# Mainboard_V1_0_Ethernet.net
KiCad netlist of a schematic drawn in Altium Designer
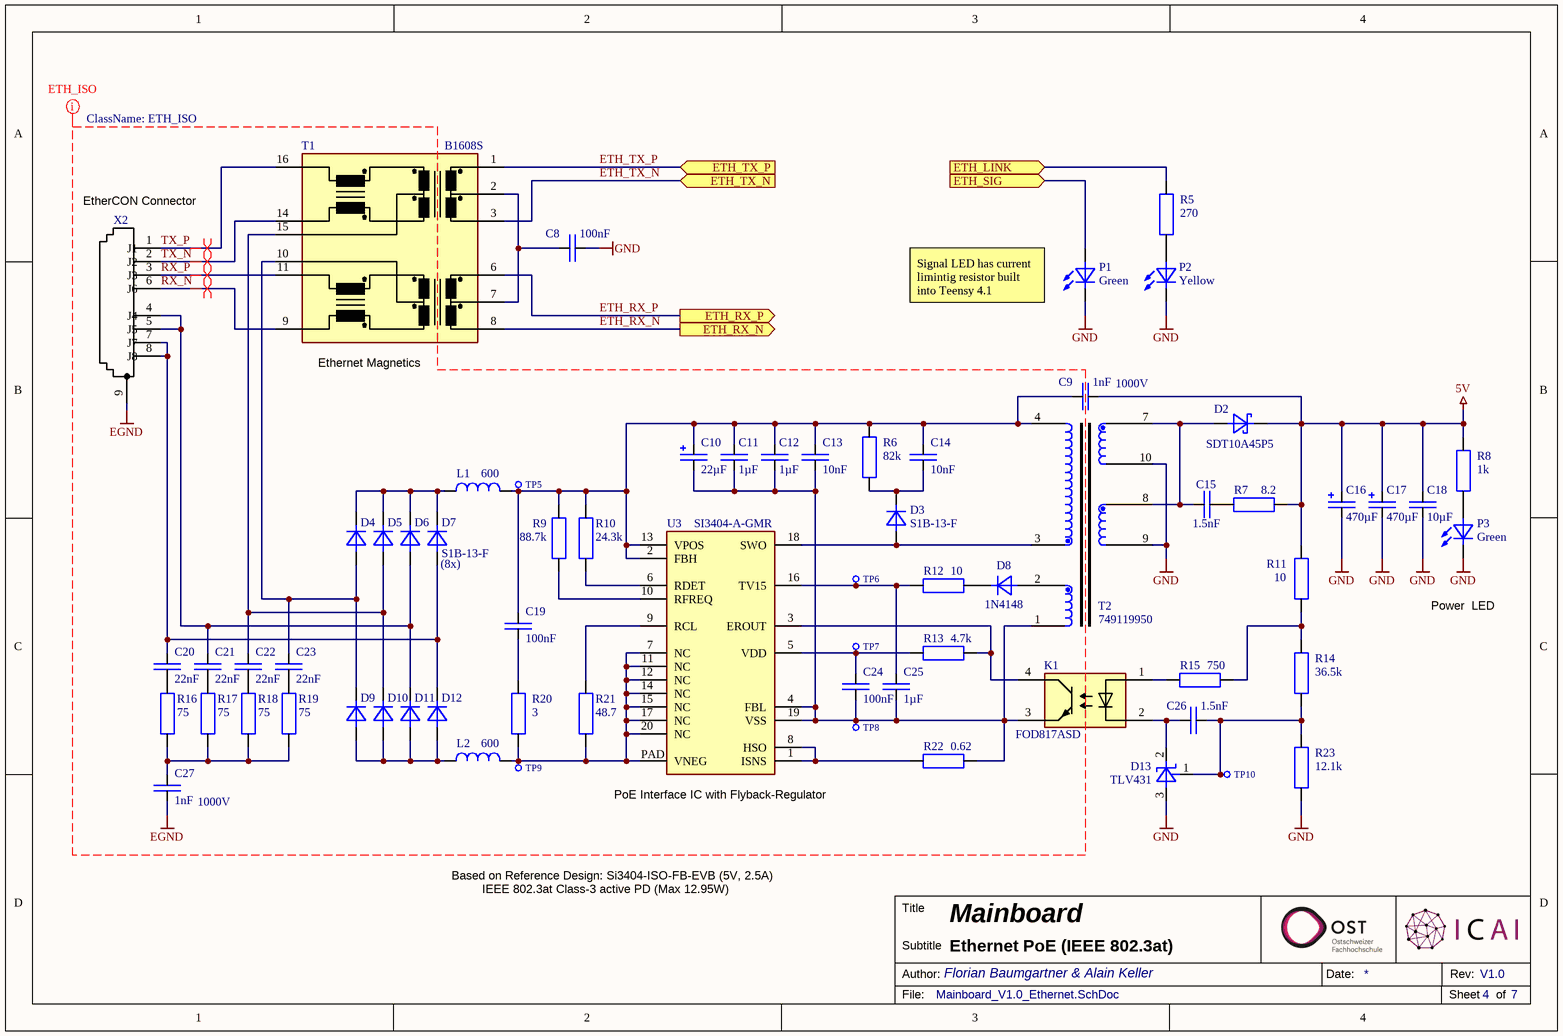
[diagram p0: Mainboard_V1.0_Ethernet.SchDoc]

(export (version "E")
  (design (tool "Eeschema 10.0.6"))
  (components
    (comp (ref "C8")
      (value "100nF")
      (footprint "SMD Keramikkondensator 0603")
      (description "SMD Ceramic Capacitor E6")
      (libsource (lib "Ceramic Capacitors-E6") (part "E6 - 100nF"))
    )
    (comp (ref "C9")
      (value "1nF")
      (footprint "SMD KERAMIKKONDENSATOR 1808")
      (description "SMD Ceramic Capacitor E6")
      (libsource (lib "Ceramic Capacitors-E6") (part "E6 - 1nF"))
    )
    (comp (ref "C10")
      (value "22µF")
      (footprint "SMD Elko 6.3x7.7")
      (description "CAP-Elko")
      (libsource (lib "TFS Integrated Library") (part "C-ELCAP"))
    )
    (comp (ref "C11")
      (value "1µF")
      (footprint "SMD Keramikkondensator 1206")
      (description "CAP-MK")
      (libsource (lib "AudioAmp") (part "C-CAPACITOR"))
    )
    (comp (ref "C12")
      (value "1µF")
      (footprint "SMD Keramikkondensator 1206")
      (description "CAP-MK")
      (libsource (lib "AudioAmp") (part "C-CAPACITOR"))
    )
    (comp (ref "C13")
      (value "10nF")
      (footprint "SMD Keramikkondensator 0603")
      (description "SMD Ceramic Capacitor E6")
      (libsource (lib "Ceramic Capacitors-E6") (part "E6 - 22nF"))
    )
    (comp (ref "C14")
      (value "10nF")
      (footprint "SMD Keramikkondensator 0603")
      (description "SMD Ceramic Capacitor E6")
      (libsource (lib "Ceramic Capacitors-E6") (part "E6 - 22nF"))
    )
    (comp (ref "C15")
      (value "1.5nF")
      (footprint "SMD Keramikkondensator 0603")
      (description "CAP-MK")
      (libsource (lib "AudioAmp") (part "C-CAPACITOR"))
    )
    (comp (ref "C16")
      (value "470µF")
      (footprint "SMD Elko 6.3x7.7")
      (description "CAP-Elko")
      (libsource (lib "TFS Integrated Library") (part "C-ELCAP"))
    )
    (comp (ref "C17")
      (value "470µF")
      (footprint "SMD Elko 6.3x7.7")
      (description "CAP-Elko")
      (libsource (lib "TFS Integrated Library") (part "C-ELCAP"))
    )
    (comp (ref "C18")
      (value "10µF")
      (footprint "SMD Keramikkondensator 1206")
      (description "SMD Ceramic Capacitor E6")
      (libsource (lib "Ceramic Capacitors-E6") (part "E6 - 10uF"))
    )
    (comp (ref "C19")
      (value "100nF")
      (footprint "SMD Keramikkondensator 0805")
      (description "SMD Ceramic Capacitor E6")
      (libsource (lib "Ceramic Capacitors-E6") (part "E6 - 22nF"))
    )
    (comp (ref "C20")
      (value "22nF")
      (footprint "SMD Keramikkondensator 0603")
      (description "SMD Ceramic Capacitor E6")
      (libsource (lib "Ceramic Capacitors-E6") (part "E6 - 22nF"))
    )
    (comp (ref "C21")
      (value "22nF")
      (footprint "SMD Keramikkondensator 0603")
      (description "SMD Ceramic Capacitor E6")
      (libsource (lib "Ceramic Capacitors-E6") (part "E6 - 22nF"))
    )
    (comp (ref "C22")
      (value "22nF")
      (footprint "SMD Keramikkondensator 0603")
      (description "SMD Ceramic Capacitor E6")
      (libsource (lib "Ceramic Capacitors-E6") (part "E6 - 22nF"))
    )
    (comp (ref "C23")
      (value "22nF")
      (footprint "SMD Keramikkondensator 0603")
      (description "SMD Ceramic Capacitor E6")
      (libsource (lib "Ceramic Capacitors-E6") (part "E6 - 22nF"))
    )
    (comp (ref "C24")
      (value "100nF")
      (footprint "SMD Keramikkondensator 0603")
      (description "SMD Ceramic Capacitor E6")
      (libsource (lib "Ceramic Capacitors-E6") (part "E6 - 100nF"))
    )
    (comp (ref "C25")
      (value "1µF")
      (footprint "SMD Keramikkondensator 0603")
      (description "CAP-MK")
      (libsource (lib "AudioAmp") (part "C-CAPACITOR"))
    )
    (comp (ref "C26")
      (value "1.5nF")
      (footprint "SMD Keramikkondensator 0603")
      (description "CAP-MK")
      (libsource (lib "AudioAmp") (part "C-CAPACITOR"))
    )
    (comp (ref "C27")
      (value "1nF")
      (footprint "SMD KERAMIKKONDENSATOR 1808")
      (description "SMD Ceramic Capacitor E6")
      (libsource (lib "Ceramic Capacitors-E6") (part "E6 - 1nF"))
    )
    (comp (ref "D2")
      (value "SDT10A45P5")
      (footprint "SMD Diode PowerDI-5")
      (description "Trench Schottky Barrier Rectifier")
      (libsource (lib "TFS Integrated Library") (part "R-DIODE{colon}SCHKY"))
    )
    (comp (ref "D3")
      (value "S1B-13-F")
      (footprint "SMD Diode DO-214-AC")
      (description "DIODE (alt V)")
      (libsource (lib "TFS Integrated Library") (part "R-DIODE"))
    )
    (comp (ref "D4")
      (value "S1B-13-F")
      (footprint "SMD Diode DO-214-AC")
      (description "DIODE (alt V)")
      (libsource (lib "TFS Integrated Library") (part "R-DIODE"))
    )
    (comp (ref "D5")
      (value "S1B-13-F")
      (footprint "SMD Diode DO-214-AC")
      (description "DIODE (alt V)")
      (libsource (lib "TFS Integrated Library") (part "R-DIODE"))
    )
    (comp (ref "D6")
      (value "S1B-13-F")
      (footprint "SMD Diode DO-214-AC")
      (description "DIODE (alt V)")
      (libsource (lib "TFS Integrated Library") (part "R-DIODE"))
    )
    (comp (ref "D7")
      (value "S1B-13-F")
      (footprint "SMD Diode DO-214-AC")
      (description "DIODE (alt V)")
      (libsource (lib "TFS Integrated Library") (part "R-DIODE"))
    )
    (comp (ref "D8")
      (value "1N4148")
      (footprint "SMD Diode SOD-123")
      (description "DIODE (alt V)")
      (libsource (lib "TFS Integrated Library") (part "R-DIODE"))
    )
    (comp (ref "D9")
      (value "S1B-13-F")
      (footprint "SMD Diode DO-214-AC")
      (description "DIODE (alt V)")
      (libsource (lib "TFS Integrated Library") (part "R-DIODE"))
    )
    (comp (ref "D10")
      (value "S1B-13-F")
      (footprint "SMD Diode DO-214-AC")
      (description "DIODE (alt V)")
      (libsource (lib "TFS Integrated Library") (part "R-DIODE"))
    )
    (comp (ref "D11")
      (value "S1B-13-F")
      (footprint "SMD Diode DO-214-AC")
      (description "DIODE (alt V)")
      (libsource (lib "TFS Integrated Library") (part "R-DIODE"))
    )
    (comp (ref "D12")
      (value "S1B-13-F")
      (footprint "SMD Diode DO-214-AC")
      (description "DIODE (alt V)")
      (libsource (lib "TFS Integrated Library") (part "R-DIODE"))
    )
    (comp (ref "D13")
      (value "TLV431")
      (footprint "SMD IC SOT-23-3")
      (description "Low-Voltage Adjustable Precision Shunt Regulator")
      (libsource (lib "Mainboard") (part "D-Voltage-Refference"))
    )
    (comp (ref "K1")
      (value "FOD817ASD")
      (footprint "SMD IC DIP-4")
      (description "Phototransistor Optocoupler")
      (libsource (lib "Mainboard") (part "K-FOD817ASD"))
    )
    (comp (ref "L1")
      (value "600")
      (footprint "SMD INDUCTOR/FERRITE 0805")
      (description "COIL (Spule alt L)")
      (libsource (lib "TFS Integrated Library") (part "R-COIL (HF)"))
    )
    (comp (ref "L2")
      (value "600")
      (footprint "SMD INDUCTOR/FERRITE 0805")
      (description "COIL (Spule alt L)")
      (libsource (lib "TFS Integrated Library") (part "R-COIL (HF)"))
    )
    (comp (ref "P1")
      (value "Green")
      (footprint "SMD LED 0603")
      (description "LED (als Lampe E / alt H)")
      (libsource (lib "TFS Integrated Library") (part "P-LED"))
    )
    (comp (ref "P2")
      (value "Yellow")
      (footprint "SMD LED 0603")
      (description "LED (als Lampe E / alt H)")
      (libsource (lib "TFS Integrated Library") (part "P-LED"))
    )
    (comp (ref "P3")
      (value "Green")
      (footprint "SMD LED 0603")
      (description "General Purpose LED")
      (libsource (lib "Fleet-Monitor") (part "LED Green 0603"))
    )
    (comp (ref "R5")
      (value "270")
      (footprint "SMD Widerstand 0603")
      (description "SMD-Widerstand 1/4W")
      (libsource (lib "Backplane_1") (part "R-RESISTOR"))
    )
    (comp (ref "R6")
      (value "82k")
      (footprint "SMD Widerstand 0603")
      (description "RES (E=Heizwiderstand B=Messwandler)")
      (libsource (lib "TFS Integrated Library") (part "R-RESISTOR"))
    )
    (comp (ref "R7")
      (value "8.2")
      (footprint "SMD Widerstand 0603")
      (description "RES (E=Heizwiderstand B=Messwandler)")
      (libsource (lib "TFS Integrated Library") (part "R-RESISTOR"))
    )
    (comp (ref "R8")
      (value "1k")
      (footprint "SMD Widerstand 0603")
      (description "RES (E=Heizwiderstand B=Messwandler)")
      (libsource (lib "") (part "R-RESISTOR_3"))
    )
    (comp (ref "R9")
      (value "88.7k")
      (footprint "SMD Widerstand 0603")
      (description "RES (E=Heizwiderstand B=Messwandler)")
      (libsource (lib "TFS Integrated Library") (part "R-RESISTOR"))
    )
    (comp (ref "R10")
      (value "24.3k")
      (footprint "SMD Widerstand 0603")
      (description "RES (E=Heizwiderstand B=Messwandler)")
      (libsource (lib "TFS Integrated Library") (part "R-RESISTOR"))
    )
    (comp (ref "R11")
      (value "10")
      (footprint "SMD Widerstand 0603")
      (description "RES (E=Heizwiderstand B=Messwandler)")
      (libsource (lib "") (part "R-RESISTOR_2"))
    )
    (comp (ref "R12")
      (value "10")
      (footprint "SMD Widerstand 0603")
      (description "RES (E=Heizwiderstand B=Messwandler)")
      (libsource (lib "TFS Integrated Library") (part "R-RESISTOR"))
    )
    (comp (ref "R13")
      (value "4.7k")
      (footprint "SMD Widerstand 0603")
      (description "RES (E=Heizwiderstand B=Messwandler)")
      (libsource (lib "") (part "R-RESISTOR_2"))
    )
    (comp (ref "R14")
      (value "36.5k")
      (footprint "SMD Widerstand 0603")
      (description "RES (E=Heizwiderstand B=Messwandler)")
      (libsource (lib "TFS Integrated Library") (part "R-RESISTOR"))
    )
    (comp (ref "R15")
      (value "750")
      (footprint "SMD Widerstand 0603")
      (description "RES (E=Heizwiderstand B=Messwandler)")
      (libsource (lib "") (part "R-RESISTOR_1"))
    )
    (comp (ref "R16")
      (value "75")
      (footprint "SMD Widerstand 0603")
      (description "RES (E=Heizwiderstand B=Messwandler)")
      (libsource (lib "TFS Integrated Library") (part "R-RESISTOR"))
    )
    (comp (ref "R17")
      (value "75")
      (footprint "SMD Widerstand 0603")
      (description "RES (E=Heizwiderstand B=Messwandler)")
      (libsource (lib "TFS Integrated Library") (part "R-RESISTOR"))
    )
    (comp (ref "R18")
      (value "75")
      (footprint "SMD Widerstand 0603")
      (description "RES (E=Heizwiderstand B=Messwandler)")
      (libsource (lib "TFS Integrated Library") (part "R-RESISTOR"))
    )
    (comp (ref "R19")
      (value "75")
      (footprint "SMD Widerstand 0603")
      (description "RES (E=Heizwiderstand B=Messwandler)")
      (libsource (lib "TFS Integrated Library") (part "R-RESISTOR"))
    )
    (comp (ref "R20")
      (value "3")
      (footprint "SMD Widerstand 0603")
      (description "RES (E=Heizwiderstand B=Messwandler)")
      (libsource (lib "TFS Integrated Library") (part "R-RESISTOR"))
    )
    (comp (ref "R21")
      (value "48.7")
      (footprint "SMD Widerstand 0603")
      (description "RES (E=Heizwiderstand B=Messwandler)")
      (libsource (lib "TFS Integrated Library") (part "R-RESISTOR"))
    )
    (comp (ref "R22")
      (value "0.62")
      (footprint "SMD Widerstand 0603")
      (description "RES (E=Heizwiderstand B=Messwandler)")
      (libsource (lib "") (part "R-RESISTOR_1"))
    )
    (comp (ref "R23")
      (value "12.1k")
      (footprint "SMD Widerstand 0603")
      (description "RES (E=Heizwiderstand B=Messwandler)")
      (libsource (lib "TFS Integrated Library") (part "R-RESISTOR"))
    )
    (comp (ref "T1")
      (value "B1608S")
      (footprint "SMD Transformer 500x375")
      (description "LAN 10/100 Base-T Pulse Transformer with PoE")
      (libsource (lib "Mainboard") (part "T-B1608S"))
    )
    (comp (ref "T2")
      (value "749119950")
      (footprint "SMD Transformer 749119950")
      (description "PoE Power Transformer")
      (libsource (lib "Mainboard") (part "T-Transformer_749119950"))
    )
    (comp (ref "TP5")
      (value "X-TP")
      (footprint "THT Testpunkt Ø1mm")
      (description "Testpunkt")
      (libsource (lib "VLD-Monitor_V1.0") (part "X-TP"))
    )
    (comp (ref "TP6")
      (value "X-TP")
      (footprint "THT Testpunkt Ø1mm")
      (description "Testpunkt")
      (libsource (lib "VLD-Monitor_V1.0") (part "X-TP"))
    )
    (comp (ref "TP7")
      (value "X-TP")
      (footprint "THT Testpunkt Ø1mm")
      (description "Testpunkt")
      (libsource (lib "VLD-Monitor_V1.0") (part "X-TP"))
    )
    (comp (ref "TP8")
      (value "X-TP")
      (footprint "THT Testpunkt Ø1mm")
      (description "Testpunkt")
      (libsource (lib "VLD-Monitor_V1.0") (part "X-TP"))
    )
    (comp (ref "TP9")
      (value "X-TP")
      (footprint "THT Testpunkt Ø1mm")
      (description "Testpunkt")
      (libsource (lib "VLD-Monitor_V1.0") (part "X-TP"))
    )
    (comp (ref "TP10")
      (value "X-TP")
      (footprint "THT Testpunkt Ø1mm")
      (description "Testpunkt")
      (libsource (lib "VLD-Monitor_V1.0") (part "X-TP"))
    )
    (comp (ref "U3")
      (value "SI3404-A-GMR")
      (footprint "SMD IC QFN-20")
      (description "IEEE 802.3 Type 1-Compliant POE PD Interface")
      (libsource (lib "Mainboard") (part "U-SI3404-A-GMR"))
    )
    (comp (ref "X2")
      (value "NE8FBV-C5-LED1-S")
      (footprint "THT CONNECTOR NE8FBV-C5-LED1-S")
      (description "RJ45 etherCON (Cat 5e)")
      (libsource (lib "Mainboard") (part "X-NE8FBV-C5-LED1-S"))
    )
  )
  (nets
    (net (code "1") (name "/ETH_LINK") (class "Default")
      (node (ref "R5") (pin "1") (pinfunction "1_1") (pintype "passive"))
    )
    (net (code "2") (name "/ETH_RX_N") (class "Default")
      (node (ref "T1") (pin "8") (pinfunction "RD-_8") (pintype "passive"))
    )
    (net (code "3") (name "/ETH_RX_P") (class "Default")
      (node (ref "T1") (pin "6") (pinfunction "RD+_6") (pintype "passive"))
    )
    (net (code "4") (name "/ETH_SIG") (class "Default")
      (node (ref "P1") (pin "A") (pinfunction "A_A") (pintype "passive"))
    )
    (net (code "5") (name "/ETH_TX_N") (class "Default")
      (node (ref "T1") (pin "3") (pinfunction "TD-_3") (pintype "passive"))
    )
    (net (code "6") (name "/ETH_TX_P") (class "Default")
      (node (ref "T1") (pin "1") (pinfunction "TD+_1") (pintype "passive"))
    )
    (net (code "7") (name "/RX_N") (class "Default")
      (node (ref "T1") (pin "9") (pinfunction "RX-_9") (pintype "passive"))
      (node (ref "X2") (pin "6") (pinfunction "6_6") (pintype "passive"))
    )
    (net (code "8") (name "/RX_P") (class "Default")
      (node (ref "T1") (pin "11") (pinfunction "RX+_11") (pintype "passive"))
      (node (ref "X2") (pin "3") (pinfunction "3_3") (pintype "passive"))
    )
    (net (code "9") (name "/TX_N") (class "Default")
      (node (ref "T1") (pin "14") (pinfunction "TX-_14") (pintype "passive"))
      (node (ref "X2") (pin "2") (pinfunction "2_2") (pintype "passive"))
    )
    (net (code "10") (name "/TX_P") (class "Default")
      (node (ref "T1") (pin "16") (pinfunction "TX+_16") (pintype "passive"))
      (node (ref "X2") (pin "1") (pinfunction "1_1") (pintype "passive"))
    )
    (net (code "11") (name "5V") (class "Default")
      (node (ref "C16") (pin "P") (pinfunction "+_P") (pintype "passive"))
      (node (ref "C17") (pin "P") (pinfunction "+_P") (pintype "passive"))
      (node (ref "C18") (pin "2") (pinfunction "2_2") (pintype "passive"))
      (node (ref "C9") (pin "1") (pinfunction "1_1") (pintype "passive"))
      (node (ref "D2") (pin "K") (pinfunction "K_K") (pintype "passive"))
      (node (ref "R11") (pin "1") (pinfunction "1_1") (pintype "passive"))
      (node (ref "R7") (pin "1") (pinfunction "1_1") (pintype "passive"))
      (node (ref "R8") (pin "2") (pinfunction "2_2") (pintype "passive"))
    )
    (net (code "12") (name "EGND") (class "Default")
      (node (ref "C27") (pin "1") (pinfunction "1_1") (pintype "passive"))
      (node (ref "X2") (pin "9") (pinfunction "9_9") (pintype "passive"))
    )
    (net (code "13") (name "GND") (class "Default")
      (node (ref "C16") (pin "M") (pinfunction "-_M") (pintype "passive"))
      (node (ref "C17") (pin "M") (pinfunction "-_M") (pintype "passive"))
      (node (ref "C18") (pin "1") (pinfunction "1_1") (pintype "passive"))
      (node (ref "C8") (pin "2") (pinfunction "2_2") (pintype "passive"))
      (node (ref "D13") (pin "3") (pinfunction "A_3") (pintype "passive"))
      (node (ref "P1") (pin "K") (pinfunction "K_K") (pintype "passive"))
      (node (ref "P2") (pin "K") (pinfunction "K_K") (pintype "passive"))
      (node (ref "P3") (pin "K") (pinfunction "K_K") (pintype "passive"))
      (node (ref "R23") (pin "2") (pinfunction "2_2") (pintype "passive"))
      (node (ref "T2") (pin "10") (pinfunction "10_10") (pintype "passive"))
      (node (ref "T2") (pin "9") (pinfunction "9_9") (pintype "passive"))
    )
    (net (code "14") (name "Net-(C10-+)") (class "Default")
      (node (ref "C10") (pin "P") (pinfunction "+_P") (pintype "passive"))
      (node (ref "C11") (pin "2") (pinfunction "2_2") (pintype "passive"))
      (node (ref "C12") (pin "2") (pinfunction "2_2") (pintype "passive"))
      (node (ref "C13") (pin "1") (pinfunction "1_1") (pintype "passive"))
      (node (ref "C14") (pin "1") (pinfunction "1_1") (pintype "passive"))
      (node (ref "C19") (pin "1") (pinfunction "1_1") (pintype "passive"))
      (node (ref "C9") (pin "2") (pinfunction "2_2") (pintype "passive"))
      (node (ref "L1") (pin "2") (pinfunction "2_2") (pintype "passive"))
      (node (ref "R10") (pin "1") (pinfunction "1_1") (pintype "passive"))
      (node (ref "R6") (pin "1") (pinfunction "1_1") (pintype "passive"))
      (node (ref "R9") (pin "1") (pinfunction "1_1") (pintype "passive"))
      (node (ref "T2") (pin "4") (pinfunction "4_4") (pintype "passive"))
      (node (ref "TP5") (pin "1") (pinfunction "1_1") (pintype "passive"))
      (node (ref "U3") (pin "13") (pinfunction "VPOS_13") (pintype "power_in"))
      (node (ref "U3") (pin "2") (pinfunction "FBH_2") (pintype "passive"))
    )
    (net (code "15") (name "Net-(C10--)") (class "Default")
      (node (ref "C10") (pin "M") (pinfunction "-_M") (pintype "passive"))
      (node (ref "C11") (pin "1") (pinfunction "1_1") (pintype "passive"))
      (node (ref "C12") (pin "1") (pinfunction "1_1") (pintype "passive"))
      (node (ref "C13") (pin "2") (pinfunction "2_2") (pintype "passive"))
      (node (ref "C24") (pin "2") (pinfunction "2_2") (pintype "passive"))
      (node (ref "C25") (pin "1") (pinfunction "1_1") (pintype "passive"))
      (node (ref "K1") (pin "3") (pinfunction "TE_3") (pintype "passive"))
      (node (ref "R22") (pin "2") (pinfunction "2_2") (pintype "passive"))
      (node (ref "T2") (pin "1") (pinfunction "1_1") (pintype "passive"))
      (node (ref "TP8") (pin "1") (pinfunction "1_1") (pintype "passive"))
      (node (ref "U3") (pin "19") (pinfunction "VSS_19") (pintype "power_in"))
      (node (ref "U3") (pin "4") (pinfunction "FBL_4") (pintype "passive"))
    )
    (net (code "16") (name "Net-(C14-Pad2)") (class "Default")
      (node (ref "C14") (pin "2") (pinfunction "2_2") (pintype "passive"))
      (node (ref "D3") (pin "K") (pinfunction "K_K") (pintype "passive"))
      (node (ref "R6") (pin "2") (pinfunction "2_2") (pintype "passive"))
    )
    (net (code "17") (name "Net-(C15-Pad1)") (class "Default")
      (node (ref "C15") (pin "1") (pinfunction "1_1") (pintype "passive"))
      (node (ref "R7") (pin "2") (pinfunction "2_2") (pintype "passive"))
    )
    (net (code "18") (name "Net-(C15-Pad2)") (class "Default")
      (node (ref "C15") (pin "2") (pinfunction "2_2") (pintype "passive"))
      (node (ref "D2") (pin "A") (pinfunction "A_A") (pintype "passive"))
      (node (ref "T2") (pin "7") (pinfunction "7_7") (pintype "passive"))
      (node (ref "T2") (pin "8") (pinfunction "8_8") (pintype "passive"))
    )
    (net (code "19") (name "Net-(C19-Pad2)") (class "Default")
      (node (ref "C19") (pin "2") (pinfunction "2_2") (pintype "passive"))
      (node (ref "R20") (pin "1") (pinfunction "1_1") (pintype "passive"))
    )
    (net (code "20") (name "Net-(C20-Pad1)") (class "Default")
      (node (ref "C20") (pin "1") (pinfunction "1_1") (pintype "passive"))
      (node (ref "D12") (pin "K") (pinfunction "K_K") (pintype "passive"))
      (node (ref "D7") (pin "A") (pinfunction "A_A") (pintype "passive"))
      (node (ref "X2") (pin "7") (pinfunction "7_7") (pintype "passive"))
      (node (ref "X2") (pin "8") (pinfunction "8_8") (pintype "passive"))
    )
    (net (code "21") (name "Net-(C20-Pad2)") (class "Default")
      (node (ref "C20") (pin "2") (pinfunction "2_2") (pintype "passive"))
      (node (ref "R16") (pin "1") (pinfunction "1_1") (pintype "passive"))
    )
    (net (code "22") (name "Net-(C21-Pad1)") (class "Default")
      (node (ref "C21") (pin "1") (pinfunction "1_1") (pintype "passive"))
      (node (ref "D11") (pin "K") (pinfunction "K_K") (pintype "passive"))
      (node (ref "D6") (pin "A") (pinfunction "A_A") (pintype "passive"))
      (node (ref "X2") (pin "4") (pinfunction "4_4") (pintype "passive"))
      (node (ref "X2") (pin "5") (pinfunction "5_5") (pintype "passive"))
    )
    (net (code "23") (name "Net-(C21-Pad2)") (class "Default")
      (node (ref "C21") (pin "2") (pinfunction "2_2") (pintype "passive"))
      (node (ref "R17") (pin "1") (pinfunction "1_1") (pintype "passive"))
    )
    (net (code "24") (name "Net-(C22-Pad2)") (class "Default")
      (node (ref "C22") (pin "2") (pinfunction "2_2") (pintype "passive"))
      (node (ref "R18") (pin "1") (pinfunction "1_1") (pintype "passive"))
    )
    (net (code "25") (name "Net-(C23-Pad2)") (class "Default")
      (node (ref "C23") (pin "2") (pinfunction "2_2") (pintype "passive"))
      (node (ref "R19") (pin "1") (pinfunction "1_1") (pintype "passive"))
    )
    (net (code "26") (name "Net-(C27-Pad2)") (class "Default")
      (node (ref "C27") (pin "2") (pinfunction "2_2") (pintype "passive"))
      (node (ref "R16") (pin "2") (pinfunction "2_2") (pintype "passive"))
      (node (ref "R17") (pin "2") (pinfunction "2_2") (pintype "passive"))
      (node (ref "R18") (pin "2") (pinfunction "2_2") (pintype "passive"))
      (node (ref "R19") (pin "2") (pinfunction "2_2") (pintype "passive"))
    )
    (net (code "27") (name "Net-(D4-PadK)") (class "Default")
      (node (ref "D4") (pin "K") (pinfunction "K_K") (pintype "passive"))
      (node (ref "D5") (pin "K") (pinfunction "K_K") (pintype "passive"))
      (node (ref "D6") (pin "K") (pinfunction "K_K") (pintype "passive"))
      (node (ref "D7") (pin "K") (pinfunction "K_K") (pintype "passive"))
      (node (ref "L1") (pin "1") (pinfunction "1_1") (pintype "passive"))
    )
    (net (code "28") (name "Net-(D8-PadA)") (class "Default")
      (node (ref "D8") (pin "A") (pinfunction "A_A") (pintype "passive"))
      (node (ref "T2") (pin "2") (pinfunction "2_2") (pintype "passive"))
    )
    (net (code "29") (name "Net-(D8-PadK)") (class "Default")
      (node (ref "D8") (pin "K") (pinfunction "K_K") (pintype "passive"))
      (node (ref "R12") (pin "1") (pinfunction "1_1") (pintype "passive"))
    )
    (net (code "30") (name "Net-(D10-PadA)") (class "Default")
      (node (ref "D10") (pin "A") (pinfunction "A_A") (pintype "passive"))
      (node (ref "D11") (pin "A") (pinfunction "A_A") (pintype "passive"))
      (node (ref "D12") (pin "A") (pinfunction "A_A") (pintype "passive"))
      (node (ref "D9") (pin "A") (pinfunction "A_A") (pintype "passive"))
      (node (ref "L2") (pin "1") (pinfunction "1_1") (pintype "passive"))
    )
    (net (code "31") (name "Net-(D13-C)") (class "Default")
      (node (ref "C26") (pin "2") (pinfunction "2_2") (pintype "passive"))
      (node (ref "D13") (pin "2") (pinfunction "C_2") (pintype "passive"))
      (node (ref "K1") (pin "2") (pinfunction "LC_2") (pintype "passive"))
    )
    (net (code "32") (name "Net-(D13-REF)") (class "Default")
      (node (ref "C26") (pin "1") (pinfunction "1_1") (pintype "passive"))
      (node (ref "D13") (pin "1") (pinfunction "REF_1") (pintype "passive"))
      (node (ref "R14") (pin "2") (pinfunction "2_2") (pintype "passive"))
      (node (ref "R23") (pin "1") (pinfunction "1_1") (pintype "passive"))
      (node (ref "TP10") (pin "1") (pinfunction "1_1") (pintype "passive"))
    )
    (net (code "33") (name "Net-(K1-LA)") (class "Default")
      (node (ref "K1") (pin "1") (pinfunction "LA_1") (pintype "passive"))
      (node (ref "R15") (pin "1") (pinfunction "1_1") (pintype "passive"))
    )
    (net (code "34") (name "Net-(K1-TC)") (class "Default")
      (node (ref "K1") (pin "4") (pinfunction "TC_4") (pintype "passive"))
      (node (ref "R13") (pin "1") (pinfunction "1_1") (pintype "passive"))
      (node (ref "U3") (pin "3") (pinfunction "EROUT_3") (pintype "passive"))
    )
    (net (code "35") (name "Net-(P2-PadA)") (class "Default")
      (node (ref "P2") (pin "A") (pinfunction "A_A") (pintype "passive"))
      (node (ref "R5") (pin "2") (pinfunction "2_2") (pintype "passive"))
    )
    (net (code "36") (name "Net-(P3-PadA)") (class "Default")
      (node (ref "P3") (pin "A") (pinfunction "A_A") (pintype "passive"))
      (node (ref "R8") (pin "1") (pinfunction "1_1") (pintype "passive"))
    )
    (net (code "37") (name "Net-(R11-Pad2)") (class "Default")
      (node (ref "R11") (pin "2") (pinfunction "2_2") (pintype "passive"))
      (node (ref "R14") (pin "1") (pinfunction "1_1") (pintype "passive"))
      (node (ref "R15") (pin "2") (pinfunction "2_2") (pintype "passive"))
    )
    (net (code "38") (name "Net-(T1-RCT)") (class "Default")
      (node (ref "C8") (pin "1") (pinfunction "1_1") (pintype "passive"))
      (node (ref "T1") (pin "2") (pinfunction "TCT_2") (pintype "passive"))
      (node (ref "T1") (pin "7") (pinfunction "RCT_7") (pintype "passive"))
    )
    (net (code "39") (name "Net-(T1-RXCT)") (class "Default")
      (node (ref "C23") (pin "1") (pinfunction "1_1") (pintype "passive"))
      (node (ref "D4") (pin "A") (pinfunction "A_A") (pintype "passive"))
      (node (ref "D9") (pin "K") (pinfunction "K_K") (pintype "passive"))
      (node (ref "T1") (pin "10") (pinfunction "RXCT_10") (pintype "passive"))
    )
    (net (code "40") (name "Net-(T1-TXCT)") (class "Default")
      (node (ref "C22") (pin "1") (pinfunction "1_1") (pintype "passive"))
      (node (ref "D10") (pin "K") (pinfunction "K_K") (pintype "passive"))
      (node (ref "D5") (pin "A") (pinfunction "A_A") (pintype "passive"))
      (node (ref "T1") (pin "15") (pinfunction "TXCT_15") (pintype "passive"))
    )
    (net (code "41") (name "Net-(U3-HSO)") (class "Default")
      (node (ref "R22") (pin "1") (pinfunction "1_1") (pintype "passive"))
      (node (ref "U3") (pin "1") (pinfunction "ISNS_1") (pintype "passive"))
      (node (ref "U3") (pin "8") (pinfunction "HSO_8") (pintype "passive"))
    )
    (net (code "42") (name "Net-(U3-RCL)") (class "Default")
      (node (ref "R21") (pin "1") (pinfunction "1_1") (pintype "passive"))
      (node (ref "U3") (pin "9") (pinfunction "RCL_9") (pintype "passive"))
    )
    (net (code "43") (name "Net-(U3-RDET)") (class "Default")
      (node (ref "R10") (pin "2") (pinfunction "2_2") (pintype "passive"))
      (node (ref "U3") (pin "6") (pinfunction "RDET_6") (pintype "passive"))
    )
    (net (code "44") (name "Net-(U3-RFREQ)") (class "Default")
      (node (ref "R9") (pin "2") (pinfunction "2_2") (pintype "passive"))
      (node (ref "U3") (pin "10") (pinfunction "RFREQ_10") (pintype "passive"))
    )
    (net (code "45") (name "Net-(U3-SWO)") (class "Default")
      (node (ref "D3") (pin "A") (pinfunction "A_A") (pintype "passive"))
      (node (ref "T2") (pin "3") (pinfunction "3_3") (pintype "passive"))
      (node (ref "U3") (pin "18") (pinfunction "SWO_18") (pintype "passive"))
    )
    (net (code "46") (name "Net-(U3-TV15)") (class "Default")
      (node (ref "C25") (pin "2") (pinfunction "2_2") (pintype "passive"))
      (node (ref "R12") (pin "2") (pinfunction "2_2") (pintype "passive"))
      (node (ref "TP6") (pin "1") (pinfunction "1_1") (pintype "passive"))
      (node (ref "U3") (pin "16") (pinfunction "TV15_16") (pintype "passive"))
    )
    (net (code "47") (name "Net-(U3-VDD)") (class "Default")
      (node (ref "C24") (pin "1") (pinfunction "1_1") (pintype "passive"))
      (node (ref "R13") (pin "2") (pinfunction "2_2") (pintype "passive"))
      (node (ref "TP7") (pin "1") (pinfunction "1_1") (pintype "passive"))
      (node (ref "U3") (pin "5") (pinfunction "VDD_5") (pintype "power_in"))
    )
    (net (code "48") (name "Net-(U3-VNEG)") (class "Default")
      (node (ref "L2") (pin "2") (pinfunction "2_2") (pintype "passive"))
      (node (ref "R20") (pin "2") (pinfunction "2_2") (pintype "passive"))
      (node (ref "R21") (pin "2") (pinfunction "2_2") (pintype "passive"))
      (node (ref "TP9") (pin "1") (pinfunction "1_1") (pintype "passive"))
      (node (ref "U3") (pin "11") (pinfunction "NC_11") (pintype "passive"))
      (node (ref "U3") (pin "12") (pinfunction "NC_12") (pintype "passive"))
      (node (ref "U3") (pin "14") (pinfunction "NC_14") (pintype "passive"))
      (node (ref "U3") (pin "15") (pinfunction "NC_15") (pintype "passive"))
      (node (ref "U3") (pin "17") (pinfunction "NC_17") (pintype "passive"))
      (node (ref "U3") (pin "20") (pinfunction "NC_20") (pintype "passive"))
      (node (ref "U3") (pin "7") (pinfunction "NC_7") (pintype "passive"))
      (node (ref "U3") (pin "PAD") (pinfunction "VNEG_PAD") (pintype "power_in"))
    )
    (net (code "49") (name "unconnected-(T1-NC-Pad4)") (class "Default")
      (node (ref "T1") (pin "4") (pinfunction "NC_4") (pintype "passive"))
    )
    (net (code "50") (name "unconnected-(T1-NC-Pad5)") (class "Default")
      (node (ref "T1") (pin "5") (pinfunction "NC_5") (pintype "passive"))
    )
    (net (code "51") (name "unconnected-(T1-NC-Pad12)") (class "Default")
      (node (ref "T1") (pin "12") (pinfunction "NC_12") (pintype "passive"))
    )
    (net (code "52") (name "unconnected-(T1-NC-Pad13)") (class "Default")
      (node (ref "T1") (pin "13") (pinfunction "NC_13") (pintype "passive"))
    )
    (net (code "53") (name "unconnected-(T2-Pad5)") (class "Default")
      (node (ref "T2") (pin "5") (pinfunction "5_5") (pintype "passive"))
    )
    (net (code "54") (name "unconnected-(T2-Pad6)") (class "Default")
      (node (ref "T2") (pin "6") (pinfunction "6_6") (pintype "passive"))
    )
  )
)
